# 1_P1.net
KiCad netlist of a schematic drawn in Altium Designer
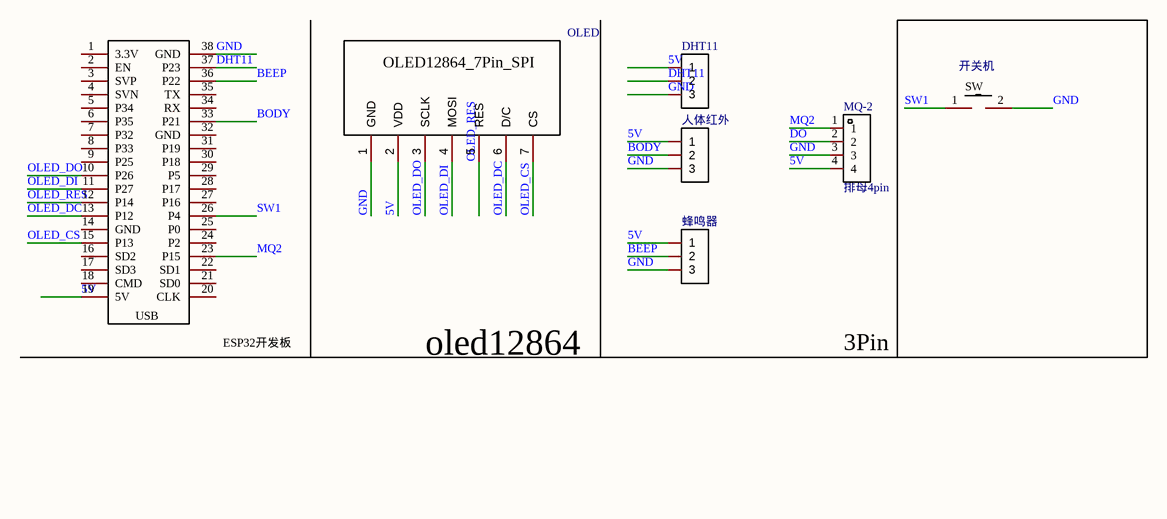
[diagram p0: 1_P1.schdoc]

(export (version "E")
  (design (tool "Eeschema 10.0.6"))
  (components
    (comp (ref "DHT11") (value "DHT11") (libsource (lib "altium-import") (part "root_0_排母3PIN_")))
    (comp (ref "ESP32_38PIN_1")
      (value "ESP32_38PIN")
      (libsource (lib "altium-import") (part "root_0_ESP32_38PIN_"))
    )
    (comp (ref "MQ-2") (value "排母4pin") (libsource (lib "altium-import") (part "root_0_排母4pin_")))
    (comp (ref "OLED")
      (value "OLED12864_7Pin_SPI")
      (libsource (lib "altium-import") (part "root_0_OLED12864_7Pin_SPI_"))
    )
    (comp (ref "人体红外") (value "人体红外") (libsource (lib "altium-import") (part "root_0_排母3PIN_")))
    (comp (ref "开关机") (value "按键") (libsource (lib "altium-import") (part "root_0_按键_")))
    (comp (ref "蜂鸣器") (value "蜂鸣器") (libsource (lib "altium-import") (part "root_0_排母3PIN_")))
  )
  (nets
    (net (code "1") (name "/5V") (class "Default")
      (node (ref "DHT11") (pin "1") (pinfunction "1_1") (pintype "passive"))
      (node (ref "ESP32_38PIN_1") (pin "19") (pinfunction "5V_19") (pintype "passive"))
      (node (ref "MQ-2") (pin "4") (pinfunction "4_4") (pintype "passive"))
      (node (ref "OLED") (pin "2") (pinfunction "VDD_2") (pintype "passive"))
      (node (ref "人体红外") (pin "1") (pinfunction "1_1") (pintype "passive"))
      (node (ref "蜂鸣器") (pin "1") (pinfunction "1_1") (pintype "passive"))
    )
    (net (code "2") (name "/BEEP") (class "Default")
      (node (ref "ESP32_38PIN_1") (pin "36") (pinfunction "P22_36") (pintype "passive"))
      (node (ref "蜂鸣器") (pin "2") (pinfunction "2_2") (pintype "passive"))
    )
    (net (code "3") (name "/BODY") (class "Default")
      (node (ref "ESP32_38PIN_1") (pin "33") (pinfunction "P21_33") (pintype "passive"))
      (node (ref "人体红外") (pin "2") (pinfunction "2_2") (pintype "passive"))
    )
    (net (code "4") (name "/DHT11") (class "Default")
      (node (ref "DHT11") (pin "2") (pinfunction "2_2") (pintype "passive"))
      (node (ref "ESP32_38PIN_1") (pin "37") (pinfunction "P23_37") (pintype "passive"))
    )
    (net (code "5") (name "/DO") (class "Default")
      (node (ref "MQ-2") (pin "2") (pinfunction "2_2") (pintype "passive"))
    )
    (net (code "6") (name "/GND") (class "Default")
      (node (ref "DHT11") (pin "3") (pinfunction "3_3") (pintype "passive"))
      (node (ref "ESP32_38PIN_1") (pin "38") (pinfunction "GND_38") (pintype "passive"))
      (node (ref "MQ-2") (pin "3") (pinfunction "3_3") (pintype "passive"))
      (node (ref "OLED") (pin "1") (pinfunction "GND_1") (pintype "passive"))
      (node (ref "人体红外") (pin "3") (pinfunction "3_3") (pintype "passive"))
      (node (ref "开关机") (pin "2") (pinfunction "2_2") (pintype "passive"))
      (node (ref "蜂鸣器") (pin "3") (pinfunction "3_3") (pintype "passive"))
    )
    (net (code "7") (name "/MQ2") (class "Default")
      (node (ref "ESP32_38PIN_1") (pin "23") (pinfunction "P15_23") (pintype "passive"))
      (node (ref "MQ-2") (pin "1") (pinfunction "1_1") (pintype "passive"))
    )
    (net (code "8") (name "/OLED_CS") (class "Default")
      (node (ref "ESP32_38PIN_1") (pin "15") (pinfunction "P13_15") (pintype "passive"))
      (node (ref "OLED") (pin "7") (pinfunction "CS_7") (pintype "passive"))
    )
    (net (code "9") (name "/OLED_DC") (class "Default")
      (node (ref "ESP32_38PIN_1") (pin "13") (pinfunction "P12_13") (pintype "passive"))
      (node (ref "OLED") (pin "6") (pinfunction "D/C_6") (pintype "passive"))
    )
    (net (code "10") (name "/OLED_DI") (class "Default")
      (node (ref "ESP32_38PIN_1") (pin "11") (pinfunction "P27_11") (pintype "passive"))
      (node (ref "OLED") (pin "4") (pinfunction "MOSI_4") (pintype "passive"))
    )
    (net (code "11") (name "/OLED_DO") (class "Default")
      (node (ref "ESP32_38PIN_1") (pin "10") (pinfunction "P26_10") (pintype "passive"))
      (node (ref "OLED") (pin "3") (pinfunction "SCLK_3") (pintype "passive"))
    )
    (net (code "12") (name "/OLED_RES") (class "Default")
      (node (ref "ESP32_38PIN_1") (pin "12") (pinfunction "P14_12") (pintype "passive"))
      (node (ref "OLED") (pin "5") (pinfunction "RES_5") (pintype "passive"))
    )
    (net (code "13") (name "/SW1") (class "Default")
      (node (ref "ESP32_38PIN_1") (pin "26") (pinfunction "P4_26") (pintype "passive"))
      (node (ref "开关机") (pin "1") (pinfunction "1_1") (pintype "passive"))
    )
    (net (code "14") (name "unconnected-(ESP32_38PIN_1-3.3V-Pad1)") (class "Default")
      (node (ref "ESP32_38PIN_1") (pin "1") (pinfunction "3.3V_1") (pintype "passive"))
    )
    (net (code "15") (name "unconnected-(ESP32_38PIN_1-CLK-Pad20)") (class "Default")
      (node (ref "ESP32_38PIN_1") (pin "20") (pinfunction "CLK_20") (pintype "passive"))
    )
    (net (code "16") (name "unconnected-(ESP32_38PIN_1-CMD-Pad18)") (class "Default")
      (node (ref "ESP32_38PIN_1") (pin "18") (pinfunction "CMD_18") (pintype "passive"))
    )
    (net (code "17") (name "unconnected-(ESP32_38PIN_1-EN-Pad2)") (class "Default")
      (node (ref "ESP32_38PIN_1") (pin "2") (pinfunction "EN_2") (pintype "passive"))
    )
    (net (code "18") (name "unconnected-(ESP32_38PIN_1-GND-Pad14)") (class "Default")
      (node (ref "ESP32_38PIN_1") (pin "14") (pinfunction "GND_14") (pintype "passive"))
    )
    (net (code "19") (name "unconnected-(ESP32_38PIN_1-GND-Pad32)") (class "Default")
      (node (ref "ESP32_38PIN_1") (pin "32") (pinfunction "GND_32") (pintype "passive"))
    )
    (net (code "20") (name "unconnected-(ESP32_38PIN_1-P0-Pad25)") (class "Default")
      (node (ref "ESP32_38PIN_1") (pin "25") (pinfunction "P0_25") (pintype "passive"))
    )
    (net (code "21") (name "unconnected-(ESP32_38PIN_1-P2-Pad24)") (class "Default")
      (node (ref "ESP32_38PIN_1") (pin "24") (pinfunction "P2_24") (pintype "passive"))
    )
    (net (code "22") (name "unconnected-(ESP32_38PIN_1-P5-Pad29)") (class "Default")
      (node (ref "ESP32_38PIN_1") (pin "29") (pinfunction "P5_29") (pintype "passive"))
    )
    (net (code "23") (name "unconnected-(ESP32_38PIN_1-P16-Pad27)") (class "Default")
      (node (ref "ESP32_38PIN_1") (pin "27") (pinfunction "P16_27") (pintype "passive"))
    )
    (net (code "24") (name "unconnected-(ESP32_38PIN_1-P17-Pad28)") (class "Default")
      (node (ref "ESP32_38PIN_1") (pin "28") (pinfunction "P17_28") (pintype "passive"))
    )
    (net (code "25") (name "unconnected-(ESP32_38PIN_1-P18-Pad30)") (class "Default")
      (node (ref "ESP32_38PIN_1") (pin "30") (pinfunction "P18_30") (pintype "passive"))
    )
    (net (code "26") (name "unconnected-(ESP32_38PIN_1-P19-Pad31)") (class "Default")
      (node (ref "ESP32_38PIN_1") (pin "31") (pinfunction "P19_31") (pintype "passive"))
    )
    (net (code "27") (name "unconnected-(ESP32_38PIN_1-P25-Pad9)") (class "Default")
      (node (ref "ESP32_38PIN_1") (pin "9") (pinfunction "P25_9") (pintype "passive"))
    )
    (net (code "28") (name "unconnected-(ESP32_38PIN_1-P32-Pad7)") (class "Default")
      (node (ref "ESP32_38PIN_1") (pin "7") (pinfunction "P32_7") (pintype "passive"))
    )
    (net (code "29") (name "unconnected-(ESP32_38PIN_1-P33-Pad8)") (class "Default")
      (node (ref "ESP32_38PIN_1") (pin "8") (pinfunction "P33_8") (pintype "passive"))
    )
    (net (code "30") (name "unconnected-(ESP32_38PIN_1-P34-Pad5)") (class "Default")
      (node (ref "ESP32_38PIN_1") (pin "5") (pinfunction "P34_5") (pintype "passive"))
    )
    (net (code "31") (name "unconnected-(ESP32_38PIN_1-P35-Pad6)") (class "Default")
      (node (ref "ESP32_38PIN_1") (pin "6") (pinfunction "P35_6") (pintype "passive"))
    )
    (net (code "32") (name "unconnected-(ESP32_38PIN_1-RX-Pad34)") (class "Default")
      (node (ref "ESP32_38PIN_1") (pin "34") (pinfunction "RX_34") (pintype "passive"))
    )
    (net (code "33") (name "unconnected-(ESP32_38PIN_1-SD0-Pad21)") (class "Default")
      (node (ref "ESP32_38PIN_1") (pin "21") (pinfunction "SD0_21") (pintype "passive"))
    )
    (net (code "34") (name "unconnected-(ESP32_38PIN_1-SD1-Pad22)") (class "Default")
      (node (ref "ESP32_38PIN_1") (pin "22") (pinfunction "SD1_22") (pintype "passive"))
    )
    (net (code "35") (name "unconnected-(ESP32_38PIN_1-SD2-Pad16)") (class "Default")
      (node (ref "ESP32_38PIN_1") (pin "16") (pinfunction "SD2_16") (pintype "passive"))
    )
    (net (code "36") (name "unconnected-(ESP32_38PIN_1-SD3-Pad17)") (class "Default")
      (node (ref "ESP32_38PIN_1") (pin "17") (pinfunction "SD3_17") (pintype "passive"))
    )
    (net (code "37") (name "unconnected-(ESP32_38PIN_1-SVN-Pad4)") (class "Default")
      (node (ref "ESP32_38PIN_1") (pin "4") (pinfunction "SVN_4") (pintype "passive"))
    )
    (net (code "38") (name "unconnected-(ESP32_38PIN_1-SVP-Pad3)") (class "Default")
      (node (ref "ESP32_38PIN_1") (pin "3") (pinfunction "SVP_3") (pintype "passive"))
    )
    (net (code "39") (name "unconnected-(ESP32_38PIN_1-TX-Pad35)") (class "Default")
      (node (ref "ESP32_38PIN_1") (pin "35") (pinfunction "TX_35") (pintype "passive"))
    )
  )
)
